# 5V_REG.net
KiCad netlist of a schematic drawn in Altium Designer
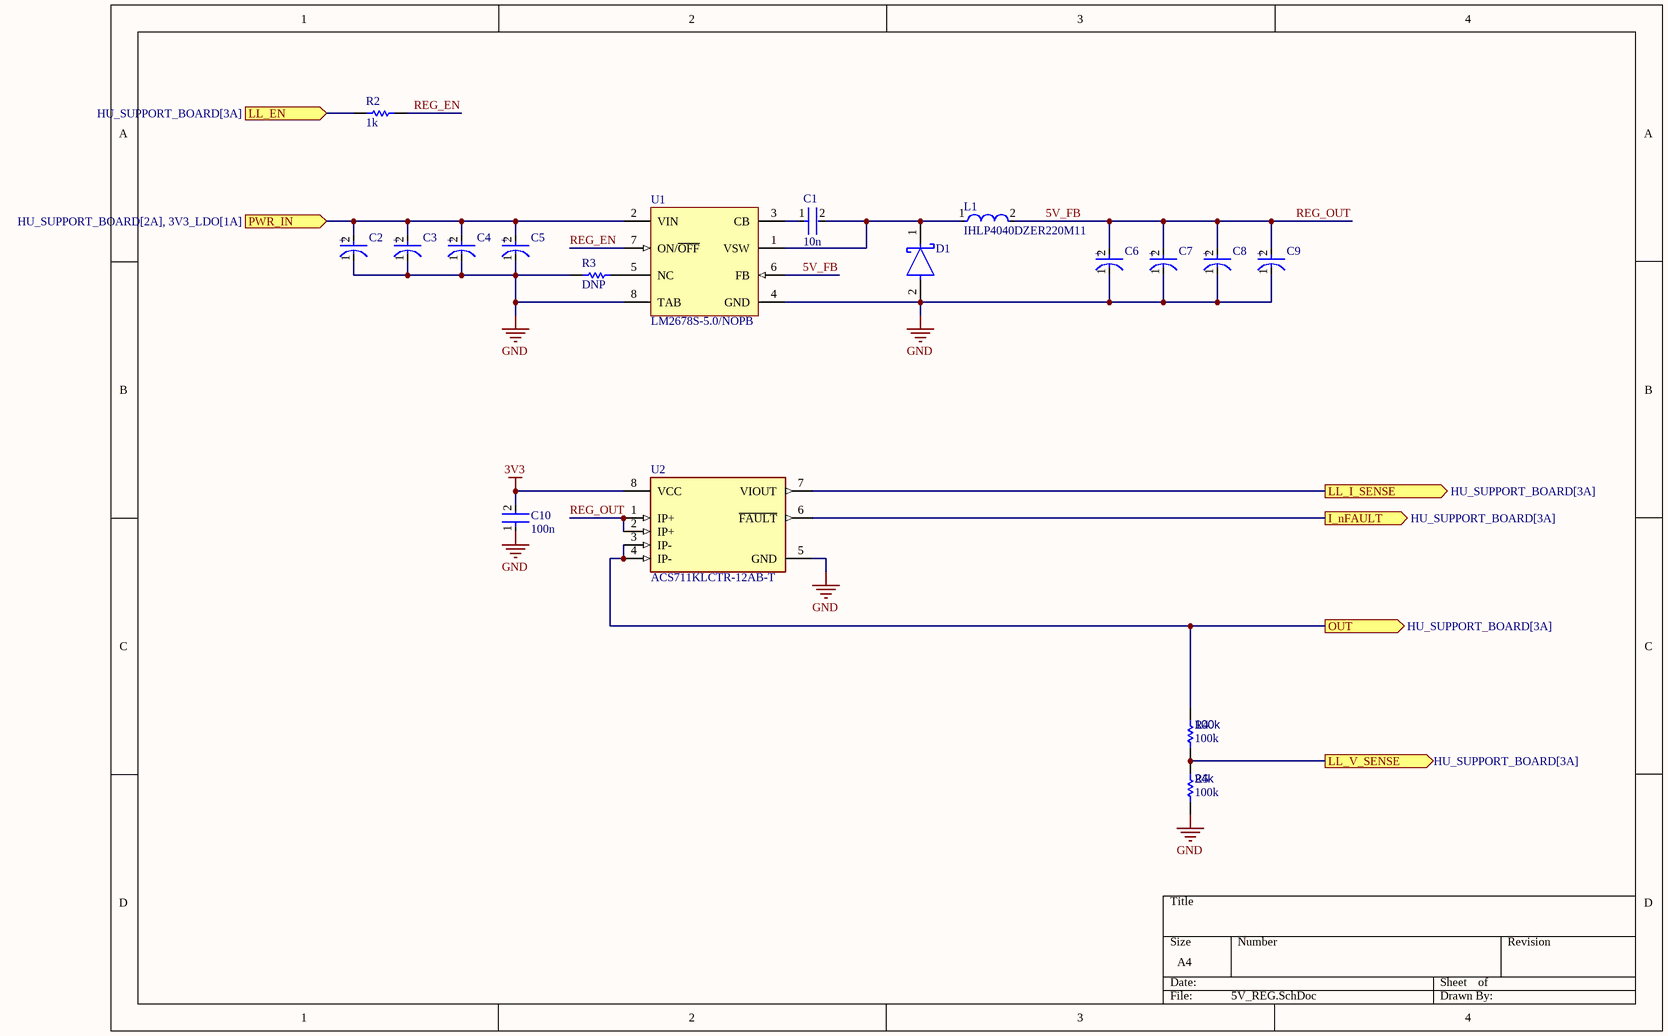
[diagram p0: 5V_REG.SchDoc]

(export (version "E")
  (design (tool "Eeschema 10.0.6"))
  (components
    (comp (ref "C1")
      (value "10n")
      (footprint "FP-0402-L_1_0_0_05-W_0_5-IPC_A")
      (description "LARGE PADS, 0402 CAP, CHANGE COMMENT TO MATCH REAL P/N")
      (libsource (lib "Space Concordia") (part "b4654b650e69147ec39a6b967a45e02"))
    )
    (comp (ref "C2")
      (value "TPSE686K025R0125")
      (footprint "FP-TPSE-MFG")
      (description "CAP TANT 68UF 10% 25V 2917")
      (fields (field (name "VOLTAGE") "25V") (field (name "TOLERANCE") "10%"))
      (libsource (lib "Altium Content Vault") (part "203bc49f2ac43e59fd269a8c329ed05"))
    )
    (comp (ref "C3")
      (value "TPSE686K025R0125")
      (footprint "FP-TPSE-MFG")
      (description "CAP TANT 68UF 10% 25V 2917")
      (fields (field (name "VOLTAGE") "25V") (field (name "TOLERANCE") "10%"))
      (libsource (lib "Altium Content Vault") (part "203bc49f2ac43e59fd269a8c329ed05"))
    )
    (comp (ref "C4")
      (value "TPSE686K025R0125")
      (footprint "FP-TPSE-MFG")
      (description "CAP TANT 68UF 10% 25V 2917")
      (fields (field (name "VOLTAGE") "25V") (field (name "TOLERANCE") "10%"))
      (libsource (lib "Altium Content Vault") (part "203bc49f2ac43e59fd269a8c329ed05"))
    )
    (comp (ref "C5")
      (value "TPSE686K025R0125")
      (footprint "FP-TPSE-MFG")
      (description "CAP TANT 68UF 10% 25V 2917")
      (fields (field (name "VOLTAGE") "25V") (field (name "TOLERANCE") "10%"))
      (libsource (lib "Altium Content Vault") (part "203bc49f2ac43e59fd269a8c329ed05"))
    )
    (comp (ref "C6")
      (value "25SVPF180M")
      (footprint "FP-OS-CON-SMT-E12-MFG")
      (description "Conductive Polymer Aluminum Solid Capacitors (OS-CON) 180uF ±20% 25V")
      (fields (field (name "VOLTAGE") "25V") (field (name "TOLERANCE") "20%"))
      (libsource (lib "Altium Content Vault") (part "a00bbbee19879c290e62620ae7e47b1"))
    )
    (comp (ref "C7")
      (value "25SVPF180M")
      (footprint "FP-OS-CON-SMT-E12-MFG")
      (description "Conductive Polymer Aluminum Solid Capacitors (OS-CON) 180uF ±20% 25V")
      (fields (field (name "VOLTAGE") "25V") (field (name "TOLERANCE") "20%"))
      (libsource (lib "Altium Content Vault") (part "a00bbbee19879c290e62620ae7e47b1"))
    )
    (comp (ref "C8")
      (value "TPSE686K025R0125")
      (footprint "FP-TPSE-MFG")
      (description "CAP TANT 68UF 10% 25V 2917")
      (fields (field (name "VOLTAGE") "25V") (field (name "TOLERANCE") "10%"))
      (libsource (lib "Altium Content Vault") (part "203bc49f2ac43e59fd269a8c329ed05"))
    )
    (comp (ref "C9")
      (value "TPSE686K025R0125")
      (footprint "FP-TPSE-MFG")
      (description "CAP TANT 68UF 10% 25V 2917")
      (fields (field (name "VOLTAGE") "25V") (field (name "TOLERANCE") "10%"))
      (libsource (lib "Altium Content Vault") (part "203bc49f2ac43e59fd269a8c329ed05"))
    )
    (comp (ref "C10")
      (value "100n")
      (footprint "FP-0402-L_1_0_0_05-W_0_5-IPC_A")
      (description "LARGE PADS, 0402 CAP, CHANGE COMMENT TO MATCH REAL P/N")
      (libsource (lib "Space Concordia") (part "b4654b650e69147ec39a6b967a45e02"))
    )
    (comp (ref "D1")
      (value "B540C-13-F")
      (footprint "FP-SMC-MFG")
      (description "DIODE SCHOTTKY 40V 5A SMC")
      (fields
        (field (name "OCTOPART") "https://octopart.com/b540c-13-f-diodes+inc.-325873")
        (field (name "MANUFACTURER") "Diodes Inc.")
      )
      (libsource (lib "Altium Content Vault") (part "1d6ec82d83fb6aee721767c19dac4b9"))
    )
    (comp (ref "L1")
      (value "IHLP4040DZER220M11")
      (footprint "FP-IHLP-4040DZ-FP_3_124x3-MFG")
      (description "Commercial Inductors, Low DCR Series 22uH 5A 66mΩ 20%")
      (fields (field (name "TOLERANCE") "20%"))
      (libsource (lib "Altium Content Vault") (part "725321dda6339637d4d059423bc1c3c"))
    )
    (comp (ref "R2")
      (value "1k")
      (footprint "R0603B")
      (description "Resistor")
      (libsource (lib "Space Concordia") (part "Resistor"))
    )
    (comp (ref "R3")
      (value "DNP")
      (footprint "R0603B")
      (description "Resistor")
      (libsource (lib "Space Concordia") (part "Resistor"))
    )
    (comp (ref "R4")
      (value "100k")
      (footprint "R0603B")
      (description "Resistor")
      (fields (field (name "ALTIUM_VALUE") "100k"))
      (libsource (lib "Space Concordia") (part "Resistor"))
    )
    (comp (ref "R5")
      (value "100k")
      (footprint "R0603B")
      (description "Resistor")
      (fields (field (name "ALTIUM_VALUE") "24k"))
      (libsource (lib "Space Concordia") (part "Resistor"))
    )
    (comp (ref "U1")
      (value "LM2678S-5.0/NOPB")
      (footprint "KTW0007B_L")
      (description "SIMPLE SWITCHER® High Efficiency 5A Step-Down Voltage Regulator, 7-pin TO-263, Pb-Free")
      (fields (field (name "MANUFACTURER") "Texas Instruments"))
      (libsource (lib "Altium Content Vault") (part "PM-REG-LM2678S"))
    )
    (comp (ref "U2")
      (value "ACS711KLCTR-12AB-T")
      (footprint "FP-LC-8-IPC_C")
      (description "SENSOR CURRENT HALL 12.5A AC/DC")
      (libsource (lib "Altium Content Vault") (part "b5e82308d4912bad35d89a98a7a92f9"))
    )
  )
  (nets
    (net (code "1") (name "/5V_FB") (class "Default")
      (node (ref "C6") (pin "2") (pinfunction "A_2") (pintype "passive"))
      (node (ref "C7") (pin "2") (pinfunction "A_2") (pintype "passive"))
      (node (ref "C8") (pin "2") (pinfunction "A_2") (pintype "passive"))
      (node (ref "C9") (pin "2") (pinfunction "A_2") (pintype "passive"))
      (node (ref "L1") (pin "2") (pinfunction "2_2") (pintype "passive"))
      (node (ref "U1") (pin "6") (pinfunction "FB_6") (pintype "input"))
      (node (ref "U2") (pin "1") (pinfunction "IP+_1") (pintype "input"))
      (node (ref "U2") (pin "2") (pinfunction "IP+_2") (pintype "input"))
    )
    (net (code "2") (name "/I_nFAULT") (class "Default")
      (node (ref "U2") (pin "6") (pinfunction "~{FAULT}_6") (pintype "output"))
    )
    (net (code "3") (name "/LL_EN") (class "Default")
      (node (ref "R2") (pin "2") (pinfunction "2_2") (pintype "passive"))
    )
    (net (code "4") (name "/LL_I_SENSE") (class "Default")
      (node (ref "U2") (pin "7") (pinfunction "VIOUT_7") (pintype "output"))
    )
    (net (code "5") (name "/LL_V_SENSE") (class "Default")
      (node (ref "R4") (pin "1") (pinfunction "1_1") (pintype "passive"))
      (node (ref "R5") (pin "2") (pinfunction "2_2") (pintype "passive"))
    )
    (net (code "6") (name "/OUT") (class "Default")
      (node (ref "R4") (pin "2") (pinfunction "2_2") (pintype "passive"))
      (node (ref "U2") (pin "3") (pinfunction "IP-_3") (pintype "input"))
      (node (ref "U2") (pin "4") (pinfunction "IP-_4") (pintype "input"))
    )
    (net (code "7") (name "/PWR_IN") (class "Default")
      (node (ref "C2") (pin "2") (pinfunction "A_2") (pintype "passive"))
      (node (ref "C3") (pin "2") (pinfunction "A_2") (pintype "passive"))
      (node (ref "C4") (pin "2") (pinfunction "A_2") (pintype "passive"))
      (node (ref "C5") (pin "2") (pinfunction "A_2") (pintype "passive"))
      (node (ref "U1") (pin "2") (pinfunction "VIN_2") (pintype "power_in"))
    )
    (net (code "8") (name "/REG_EN") (class "Default")
      (node (ref "R2") (pin "1") (pinfunction "1_1") (pintype "passive"))
      (node (ref "U1") (pin "7") (pinfunction "ON/~{OFF}_7") (pintype "input"))
    )
    (net (code "9") (name "3V3") (class "Default")
      (node (ref "C10") (pin "2") (pinfunction "2_2") (pintype "passive"))
      (node (ref "U2") (pin "8") (pinfunction "VCC_8") (pintype "power_in"))
    )
    (net (code "10") (name "GND") (class "Default")
      (node (ref "C10") (pin "1") (pinfunction "1_1") (pintype "passive"))
      (node (ref "C2") (pin "1") (pinfunction "C_1") (pintype "passive"))
      (node (ref "C3") (pin "1") (pinfunction "C_1") (pintype "passive"))
      (node (ref "C4") (pin "1") (pinfunction "C_1") (pintype "passive"))
      (node (ref "C5") (pin "1") (pinfunction "C_1") (pintype "passive"))
      (node (ref "C6") (pin "1") (pinfunction "C_1") (pintype "passive"))
      (node (ref "C7") (pin "1") (pinfunction "C_1") (pintype "passive"))
      (node (ref "C8") (pin "1") (pinfunction "C_1") (pintype "passive"))
      (node (ref "C9") (pin "1") (pinfunction "C_1") (pintype "passive"))
      (node (ref "D1") (pin "2") (pinfunction "A_2") (pintype "passive"))
      (node (ref "R3") (pin "2") (pinfunction "2_2") (pintype "passive"))
      (node (ref "R5") (pin "1") (pinfunction "1_1") (pintype "passive"))
      (node (ref "U1") (pin "4") (pinfunction "GND_4") (pintype "power_in"))
      (node (ref "U1") (pin "8") (pinfunction "TAB_8") (pintype "power_in"))
      (node (ref "U2") (pin "5") (pinfunction "GND_5") (pintype "power_in"))
    )
    (net (code "11") (name "Net-(D1-C)") (class "Default")
      (node (ref "C1") (pin "2") (pinfunction "2_2") (pintype "passive"))
      (node (ref "D1") (pin "1") (pinfunction "C_1") (pintype "passive"))
      (node (ref "L1") (pin "1") (pinfunction "1_1") (pintype "passive"))
      (node (ref "U1") (pin "1") (pinfunction "VSW_1") (pintype "power_in"))
    )
    (net (code "12") (name "Net-(U1-CB)") (class "Default")
      (node (ref "C1") (pin "1") (pinfunction "1_1") (pintype "passive"))
      (node (ref "U1") (pin "3") (pinfunction "CB_3") (pintype "passive"))
    )
    (net (code "13") (name "Net-(U1-NC)") (class "Default")
      (node (ref "R3") (pin "1") (pinfunction "1_1") (pintype "passive"))
      (node (ref "U1") (pin "5") (pinfunction "NC_5") (pintype "passive"))
    )
  )
)
